# External_Camera_HAT_Peripherals.net
KiCad netlist of a schematic drawn in Altium Designer
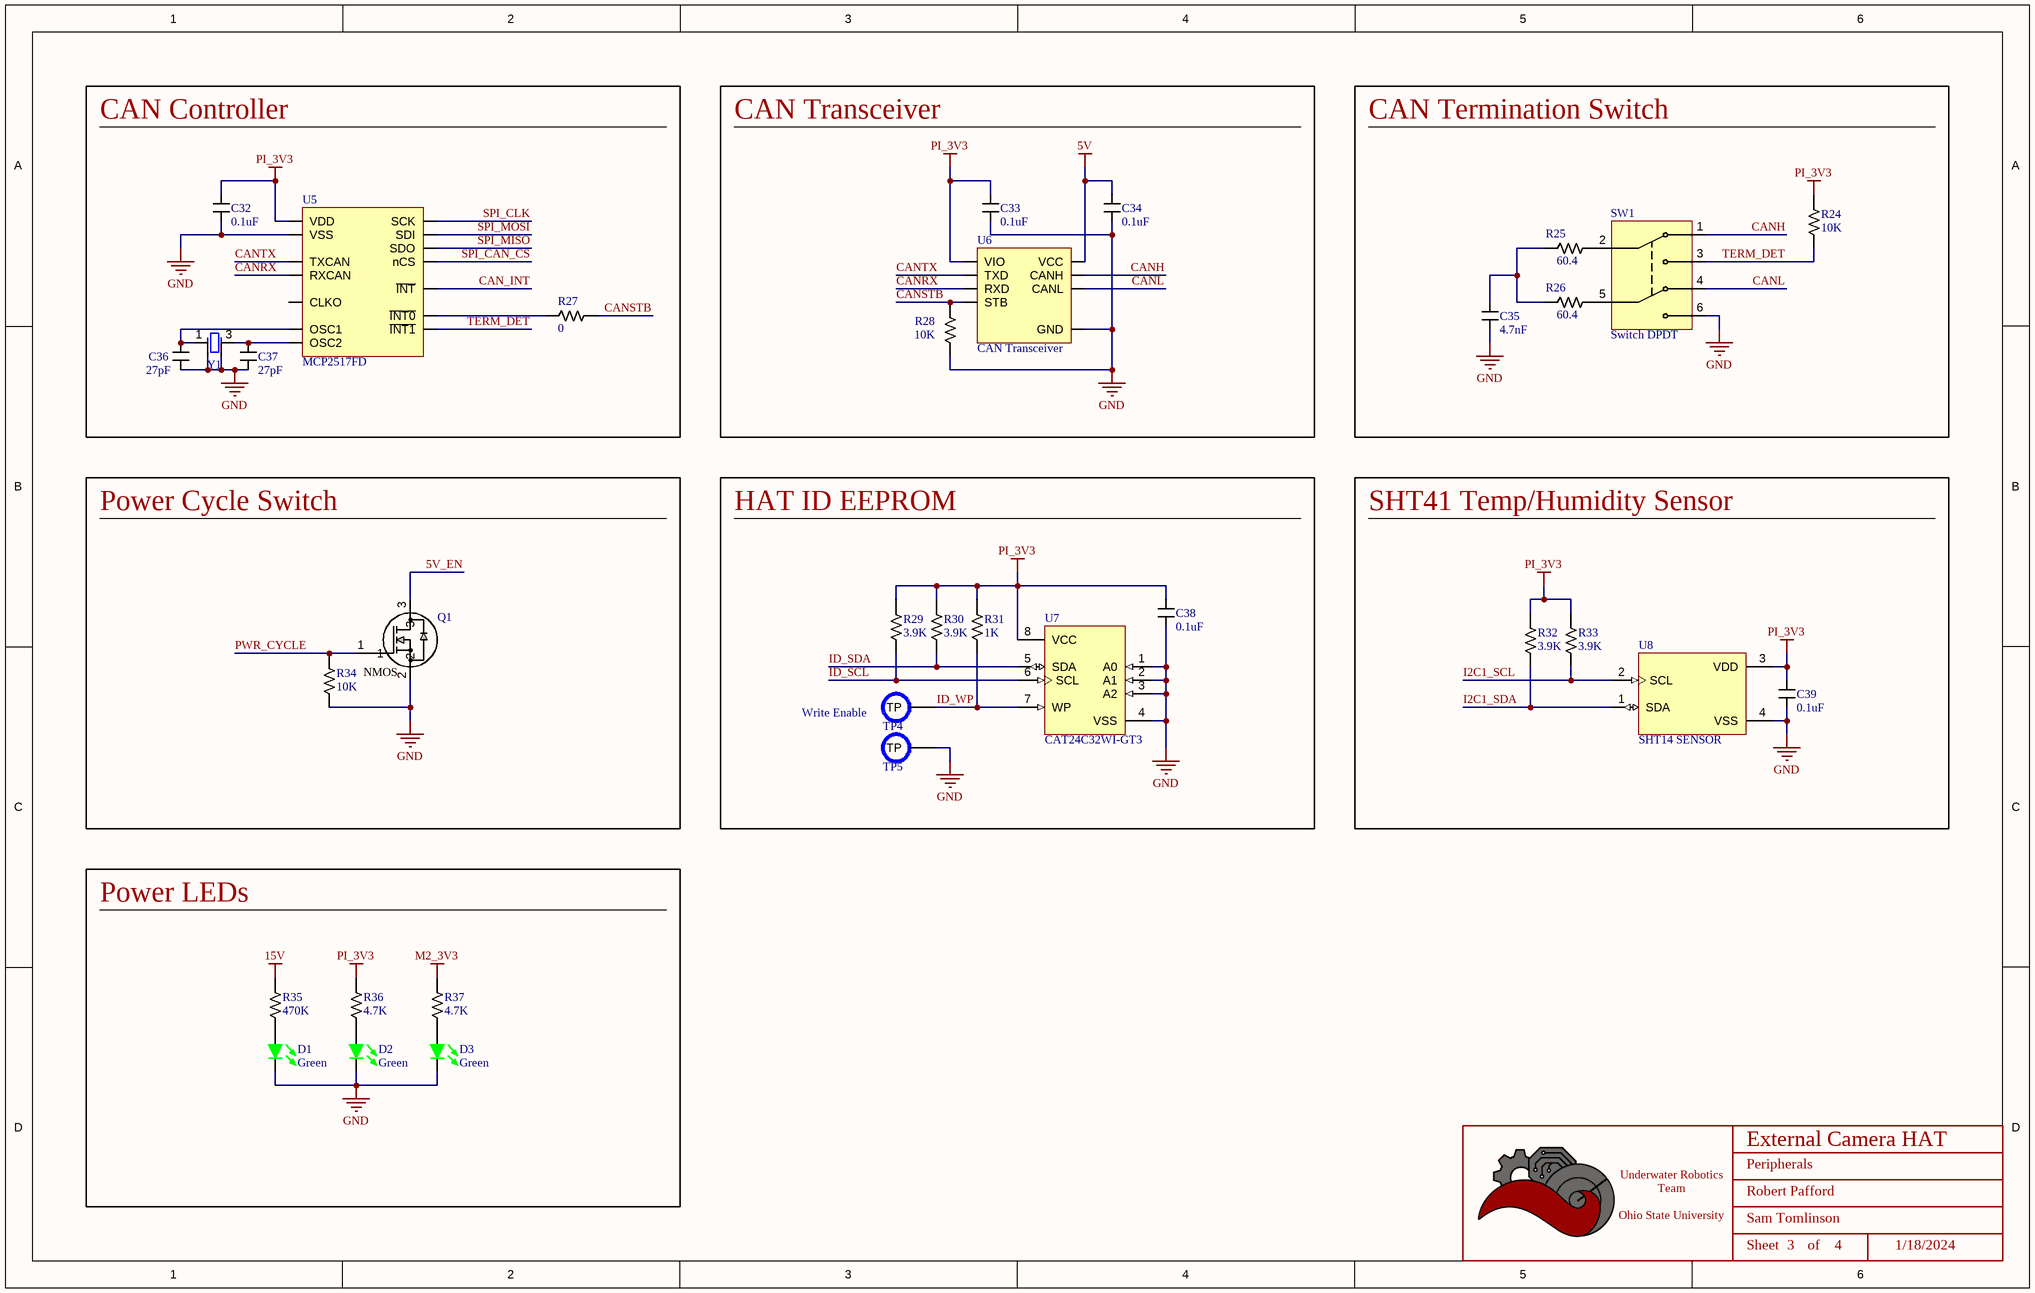
[diagram p0: External_Camera_HAT_Peripherals.SchDoc]

(export (version "E")
  (design (tool "Eeschema 10.0.6"))
  (components
    (comp (ref "C32")
      (value "0.1uF")
      (footprint "CAPACITOR_0402")
      (description "Cap 100nF 25V +/-10%\r\nCeramic 0402")
      (fields
        (field (name "TOLERANCE") "+/- 10%")
        (field (name "VOLTAGE") "25V")
        (field (name "MADE BY") "Robert Pafford")
      )
      (libsource (lib "Capacitors") (part "CAPACITOR_0.1uF_0402"))
    )
    (comp (ref "C33")
      (value "0.1uF")
      (footprint "CAPACITOR_0402")
      (description "Cap 100nF 25V +/-10%\r\nCeramic 0402")
      (fields
        (field (name "TOLERANCE") "+/- 10%")
        (field (name "VOLTAGE") "25V")
        (field (name "MADE BY") "Robert Pafford")
      )
      (libsource (lib "Capacitors") (part "CAPACITOR_0.1uF_0402"))
    )
    (comp (ref "C34")
      (value "0.1uF")
      (footprint "CAPACITOR_0402")
      (description "Cap 100nF 25V +/-10%\r\nCeramic 0402")
      (fields
        (field (name "TOLERANCE") "+/- 10%")
        (field (name "VOLTAGE") "25V")
        (field (name "MADE BY") "Robert Pafford")
      )
      (libsource (lib "Capacitors") (part "CAPACITOR_0.1uF_0402"))
    )
    (comp (ref "C35")
      (value "4.7nF")
      (footprint "CAPACITOR_0402")
      (description "4700 pF +/-10% 25V Ceramic Capacitor X7R 0402")
      (fields
        (field (name "TOLERANCE") "+/- 10%")
        (field (name "VOLTAGE") "25V")
        (field (name "MADE BY") "Robert Pafford")
      )
      (libsource (lib "Capacitors") (part "CAPACITOR_0.0047uF_0402"))
    )
    (comp (ref "C36")
      (value "27pF")
      (footprint "CAPACITOR_0402")
      (description "Cap 27pF 50V +/-5%\r\nCeramic 0402")
      (fields
        (field (name "TOLERANCE") "+/- 5%")
        (field (name "VOLTAGE") "50V")
        (field (name "MADE BY") "Robert Pafford")
      )
      (libsource (lib "Capacitors") (part "CAPACITOR_0.000027uF_0402"))
    )
    (comp (ref "C37")
      (value "27pF")
      (footprint "CAPACITOR_0402")
      (description "Cap 27pF 50V +/-5%\r\nCeramic 0402")
      (fields
        (field (name "TOLERANCE") "+/- 5%")
        (field (name "VOLTAGE") "50V")
        (field (name "MADE BY") "Robert Pafford")
      )
      (libsource (lib "Capacitors") (part "CAPACITOR_0.000027uF_0402"))
    )
    (comp (ref "C38")
      (value "0.1uF")
      (footprint "CAPACITOR_0402")
      (description "Cap 100nF 25V +/-10%\r\nCeramic 0402")
      (fields
        (field (name "TOLERANCE") "+/- 10%")
        (field (name "VOLTAGE") "25V")
        (field (name "MADE BY") "Robert Pafford")
      )
      (libsource (lib "Capacitors") (part "CAPACITOR_0.1uF_0402"))
    )
    (comp (ref "C39")
      (value "0.1uF")
      (footprint "CAPACITOR_0402")
      (description "Cap 100nF 25V +/-10%\r\nCeramic 0402")
      (fields
        (field (name "TOLERANCE") "+/- 10%")
        (field (name "VOLTAGE") "25V")
        (field (name "MADE BY") "Robert Pafford")
      )
      (libsource (lib "Capacitors") (part "CAPACITOR_0.1uF_0402"))
    )
    (comp (ref "D1")
      (value "150060GS75000")
      (footprint "LED_0603")
      (description "LED Green Vf= 3.2V If = 0.025A\r\n150060GS75000")
      (fields (field (name "COLOR") "Green") (field (name "MADE BY") "Flip B"))
      (libsource (lib "Diodes") (part "LED_Green_0603_3.2V"))
    )
    (comp (ref "D2")
      (value "150060GS75000")
      (footprint "LED_0603")
      (description "LED Green Vf= 3.2V If = 0.025A\r\n150060GS75000")
      (fields (field (name "COLOR") "Green") (field (name "MADE BY") "Flip B"))
      (libsource (lib "Diodes") (part "LED_Green_0603_3.2V"))
    )
    (comp (ref "D3")
      (value "150060GS75000")
      (footprint "LED_0603")
      (description "LED Green Vf= 3.2V If = 0.025A\r\n150060GS75000")
      (fields (field (name "COLOR") "Green") (field (name "MADE BY") "Flip B"))
      (libsource (lib "Diodes") (part "LED_Green_0603_3.2V"))
    )
    (comp (ref "Q1")
      (value "MOSFET N-CH 30V 5.8A SOT-23-3")
      (footprint "SOT-23-3")
      (description "N-Channel 30 V 5.8A (Ta) 1.4W (Ta) Surface Mount SOT-23-3")
      (fields (field (name "MANUFACTURER _PART_NUMBER") "AO3404A") (field (name "CREATED BY") "Dylan T"))
      (libsource (lib "Transistors") (part "AO3404A"))
    )
    (comp (ref "R24")
      (value "10k Ohm 1% 1/16W")
      (footprint "RESISTOR_0402")
      (description "RES 10k OHM 1% 1/16W 0402")
      (fields
        (field (name "TOLERANCE") "+/- 1%")
        (field (name "VALUE  (OHMS)") "10K")
        (field (name "MADE BY") "Robert Pafford")
      )
      (libsource (lib "Resistors") (part "RESISTOR_10K_0402"))
    )
    (comp (ref "R25")
      (value "60.4 Ohm 1% 1/16W")
      (footprint "RESISTOR_0402")
      (description "RES 60.4 OHM 1% 1/16W 0402")
      (fields
        (field (name "TOLERANCE") "+/- 1%")
        (field (name "VALUE  (OHMS)") "60.4")
        (field (name "MADE BY") "Robert Pafford")
      )
      (libsource (lib "Resistors") (part "RESISTOR_60.4_0402"))
    )
    (comp (ref "R26")
      (value "60.4 Ohm 1% 1/16W")
      (footprint "RESISTOR_0402")
      (description "RES 60.4 OHM 1% 1/16W 0402")
      (fields
        (field (name "TOLERANCE") "+/- 1%")
        (field (name "VALUE  (OHMS)") "60.4")
        (field (name "MADE BY") "Robert Pafford")
      )
      (libsource (lib "Resistors") (part "RESISTOR_60.4_0402"))
    )
    (comp (ref "R27")
      (value "0 Ohm 1% 1/16W")
      (footprint "RESISTOR_0402")
      (description "RES 0 OHM 1% 1/16W 0402")
      (fields
        (field (name "TOLERANCE") "+/- 1%")
        (field (name "VALUE  (OHMS)") "0")
        (field (name "MADE BY") "Robert Pafford")
      )
      (libsource (lib "Resistors") (part "RESISTOR_0_0402"))
    )
    (comp (ref "R28")
      (value "10k Ohm 1% 1/16W")
      (footprint "RESISTOR_0402")
      (description "RES 10k OHM 1% 1/16W 0402")
      (fields
        (field (name "TOLERANCE") "+/- 1%")
        (field (name "VALUE  (OHMS)") "10K")
        (field (name "MADE BY") "Robert Pafford")
      )
      (libsource (lib "Resistors") (part "RESISTOR_10K_0402"))
    )
    (comp (ref "R29")
      (value "3.9k Ohm 1% 1/16W")
      (footprint "RESISTOR_0402")
      (description "RES 3.9k OHM 1% 1/16W 0402")
      (fields
        (field (name "TOLERANCE") "+/- 1%")
        (field (name "VALUE  (OHMS)") "3.9K")
        (field (name "MADE BY") "Robert Pafford")
      )
      (libsource (lib "Resistors") (part "RESISTOR_3.9K_0402"))
    )
    (comp (ref "R30")
      (value "3.9k Ohm 1% 1/16W")
      (footprint "RESISTOR_0402")
      (description "RES 3.9k OHM 1% 1/16W 0402")
      (fields
        (field (name "TOLERANCE") "+/- 1%")
        (field (name "VALUE  (OHMS)") "3.9K")
        (field (name "MADE BY") "Robert Pafford")
      )
      (libsource (lib "Resistors") (part "RESISTOR_3.9K_0402"))
    )
    (comp (ref "R31")
      (value "1k Ohm 1% 1/16W")
      (footprint "RESISTOR_0402")
      (description "RES 1k OHM 1% 1/16W 0402")
      (fields
        (field (name "TOLERANCE") "+/- 1%")
        (field (name "VALUE  (OHMS)") "1K")
        (field (name "MADE BY") "Robert Pafford")
      )
      (libsource (lib "Resistors") (part "RESISTOR_1K_0402"))
    )
    (comp (ref "R32")
      (value "3.9k Ohm 1% 1/16W")
      (footprint "RESISTOR_0402")
      (description "RES 3.9k OHM 1% 1/16W 0402")
      (fields
        (field (name "TOLERANCE") "+/- 1%")
        (field (name "VALUE  (OHMS)") "3.9K")
        (field (name "MADE BY") "Robert Pafford")
      )
      (libsource (lib "Resistors") (part "RESISTOR_3.9K_0402"))
    )
    (comp (ref "R33")
      (value "3.9k Ohm 1% 1/16W")
      (footprint "RESISTOR_0402")
      (description "RES 3.9k OHM 1% 1/16W 0402")
      (fields
        (field (name "TOLERANCE") "+/- 1%")
        (field (name "VALUE  (OHMS)") "3.9K")
        (field (name "MADE BY") "Robert Pafford")
      )
      (libsource (lib "Resistors") (part "RESISTOR_3.9K_0402"))
    )
    (comp (ref "R34")
      (value "10k Ohm 1% 1/16W")
      (footprint "RESISTOR_0402")
      (description "RES 10k OHM 1% 1/16W 0402")
      (fields
        (field (name "TOLERANCE") "+/- 1%")
        (field (name "VALUE  (OHMS)") "10K")
        (field (name "MADE BY") "Robert Pafford")
      )
      (libsource (lib "Resistors") (part "RESISTOR_10K_0402"))
    )
    (comp (ref "R35")
      (value "470k Ohm 5% 1/10W")
      (footprint "RESISTOR_0603")
      (description "RES 470k OHM 5% 1/10W 0603")
      (fields
        (field (name "TOLERANCE") "+/- 5%")
        (field (name "VALUE  (OHMS)") "470K")
        (field (name "MADE BY") "Robert P")
      )
      (libsource (lib "Resistors") (part "RESISTOR_470K_0603"))
    )
    (comp (ref "R36")
      (value "4.7k Ohm 5% 1/10W")
      (footprint "RESISTOR_0603")
      (description "RES 4.7k OHM 5% 1/10W 0603")
      (fields
        (field (name "TOLERANCE") "+/- 5%")
        (field (name "VALUE  (OHMS)") "4.7K")
        (field (name "MADE BY") "Robert Pafford")
      )
      (libsource (lib "Resistors") (part "RESISTOR_4.7K_0603"))
    )
    (comp (ref "R37")
      (value "4.7k Ohm 5% 1/10W")
      (footprint "RESISTOR_0603")
      (description "RES 4.7k OHM 5% 1/10W 0603")
      (fields
        (field (name "TOLERANCE") "+/- 5%")
        (field (name "VALUE  (OHMS)") "4.7K")
        (field (name "MADE BY") "Robert Pafford")
      )
      (libsource (lib "Resistors") (part "RESISTOR_4.7K_0603"))
    )
    (comp (ref "SW1")
      (value "Switch DPDT")
      (footprint "CAS-220TA")
      (description "GOLD SWITCH FLUSH SLIDE DPDT 100MA 6V")
      (fields (field (name "MADE BY") "Robert Pafford"))
      (libsource (lib "Switches") (part "CAS-220TA_CAN_TERM"))
    )
    (comp (ref "TP4")
      (value "Write Enable")
      (footprint "TESTPOINT_1.2MM")
      (description "PCB Test Point")
      (fields (field (name "MADE BY") "Robert Pafford"))
      (libsource (lib "Connectors") (part "TESTPOINT"))
    )
    (comp (ref "TP5")
      (value "PCB Test Point")
      (footprint "TESTPOINT_1.2MM")
      (fields (field (name "MADE BY") "Robert Pafford"))
      (libsource (lib "Connectors") (part "TESTPOINT"))
    )
    (comp (ref "U5")
      (value "MCP2517FD")
      (footprint "SOIC-14")
      (description "CANbus Controller CAN 2.0 SPI Interface 14-SOIC")
      (fields (field (name "MADE BY") "Robert Pafford"))
      (libsource (lib "Integrated Circuits") (part "MCP2517FD"))
    )
    (comp (ref "U6")
      (value "CAN Transceiver")
      (footprint "SOIC-8")
      (description "CAN Interface IC High-Speed CAN Transceiver with Standby Mode")
      (fields (field (name "MADE BY") "Robert Pafford"))
      (libsource (lib "Integrated Circuits") (part "TJA1442AT"))
    )
    (comp (ref "U7")
      (value "CAT24C32WI-GT3")
      (footprint "ONSC-SOIC-8-751BD-01_M")
      (libsource (lib "Altium Content Vault") (part "ONSC-CAT24C32-SOIC-8"))
    )
    (comp (ref "U8")
      (value "SHT14 SENSOR")
      (footprint "XDCR_SHT41-AD1B-R2")
      (description "Digital Relative Humidity Temperature Sensor, Â±1.8 / max 2.5 %RH, Â±0.2 Â°C, Ultra-Low-Power")
      (fields (field (name "MP") "SHT41-AD1B-R2") (field (name "MF") "Sensirion"))
      (libsource (lib "Integrated Circuits") (part "SHT41-AD1B-R2"))
    )
    (comp (ref "Y1")
      (value "CRYSTAL 20.0000MHZ 18PF SMD")
      (footprint "4-SMD, NO LEAD CRYSTAL 3.2x2.5mm")
      (description "20 MHz ±20ppm Crystal 18pF 100 Ohms 4-SMD, No Lead (3.2x2.5mm)")
      (fields (field (name "MADE BY") "Robert Pafford"))
      (libsource (lib "Crystals") (part "CRYSTAL_20MHz_SMD"))
    )
  )
  (nets
    (net (code "1") (name "/5V_EN") (class "Default")
      (node (ref "Q1") (pin "3") (pinfunction "3_3") (pintype "passive"))
    )
    (net (code "2") (name "/CANH") (class "Default")
      (node (ref "SW1") (pin "1") (pintype "passive"))
      (node (ref "U6") (pin "7") (pinfunction "CANH_7") (pintype "passive"))
    )
    (net (code "3") (name "/CANL") (class "Default")
      (node (ref "SW1") (pin "4") (pintype "passive"))
      (node (ref "U6") (pin "6") (pinfunction "CANL_6") (pintype "passive"))
    )
    (net (code "4") (name "/CANRX") (class "Default")
      (node (ref "U5") (pin "2") (pinfunction "RXCAN_2") (pintype "passive"))
      (node (ref "U6") (pin "4") (pinfunction "RXD_4") (pintype "passive"))
    )
    (net (code "5") (name "/CANSTB") (class "Default")
      (node (ref "R27") (pin "1") (pinfunction "1_1") (pintype "passive"))
      (node (ref "R28") (pin "1") (pinfunction "1_1") (pintype "passive"))
      (node (ref "U6") (pin "8") (pinfunction "STB_8") (pintype "passive"))
    )
    (net (code "6") (name "/CANTX") (class "Default")
      (node (ref "U5") (pin "1") (pinfunction "TXCAN_1") (pintype "passive"))
      (node (ref "U6") (pin "1") (pinfunction "TXD_1") (pintype "passive"))
    )
    (net (code "7") (name "/CAN_INT") (class "Default")
      (node (ref "U5") (pin "4") (pinfunction "~{INT}_4") (pintype "passive"))
    )
    (net (code "8") (name "/I2C1_SCL") (class "Default")
      (node (ref "R33") (pin "2") (pinfunction "2_2") (pintype "passive"))
      (node (ref "U8") (pin "2") (pinfunction "SCL_2") (pintype "input"))
    )
    (net (code "9") (name "/I2C1_SDA") (class "Default")
      (node (ref "R32") (pin "2") (pinfunction "2_2") (pintype "passive"))
      (node (ref "U8") (pin "1") (pinfunction "SDA_1") (pintype "bidirectional"))
    )
    (net (code "10") (name "/ID_SCL") (class "Default")
      (node (ref "R29") (pin "2") (pinfunction "2_2") (pintype "passive"))
      (node (ref "U7") (pin "6") (pinfunction "SCL_6") (pintype "input"))
    )
    (net (code "11") (name "/ID_SDA") (class "Default")
      (node (ref "R30") (pin "2") (pinfunction "2_2") (pintype "passive"))
      (node (ref "U7") (pin "5") (pinfunction "SDA_5") (pintype "bidirectional"))
    )
    (net (code "12") (name "/ID_WP") (class "Default")
      (node (ref "R31") (pin "2") (pinfunction "2_2") (pintype "passive"))
      (node (ref "TP4") (pin "TP") (pinfunction "TP_TP") (pintype "passive"))
      (node (ref "U7") (pin "7") (pinfunction "WP_7") (pintype "input"))
    )
    (net (code "13") (name "/PWR_CYCLE") (class "Default")
      (node (ref "Q1") (pin "1") (pinfunction "1_1") (pintype "passive"))
      (node (ref "R34") (pin "1") (pinfunction "1_1") (pintype "passive"))
    )
    (net (code "14") (name "/SPI_CAN_CS") (class "Default")
      (node (ref "U5") (pin "13") (pinfunction "nCS_13") (pintype "passive"))
    )
    (net (code "15") (name "/SPI_CLK") (class "Default")
      (node (ref "U5") (pin "10") (pinfunction "SCK_10") (pintype "passive"))
    )
    (net (code "16") (name "/SPI_MISO") (class "Default")
      (node (ref "U5") (pin "12") (pinfunction "SDO_12") (pintype "passive"))
    )
    (net (code "17") (name "/SPI_MOSI") (class "Default")
      (node (ref "U5") (pin "11") (pinfunction "SDI_11") (pintype "passive"))
    )
    (net (code "18") (name "/TERM_DET") (class "Default")
      (node (ref "R24") (pin "2") (pinfunction "2_2") (pintype "passive"))
      (node (ref "SW1") (pin "3") (pintype "passive"))
      (node (ref "U5") (pin "8") (pinfunction "~{INT1}_8") (pintype "passive"))
    )
    (net (code "19") (name "5V") (class "Default")
      (node (ref "C34") (pin "1") (pinfunction "1_1") (pintype "passive"))
      (node (ref "U6") (pin "3") (pinfunction "VCC_3") (pintype "passive"))
    )
    (net (code "20") (name "15V") (class "Default")
      (node (ref "R35") (pin "1") (pinfunction "1_1") (pintype "passive"))
    )
    (net (code "21") (name "GND") (class "Default")
      (node (ref "C32") (pin "2") (pinfunction "2_2") (pintype "passive"))
      (node (ref "C33") (pin "2") (pinfunction "2_2") (pintype "passive"))
      (node (ref "C34") (pin "2") (pinfunction "2_2") (pintype "passive"))
      (node (ref "C35") (pin "1") (pinfunction "1_1") (pintype "passive"))
      (node (ref "C36") (pin "2") (pinfunction "2_2") (pintype "passive"))
      (node (ref "C37") (pin "2") (pinfunction "2_2") (pintype "passive"))
      (node (ref "C38") (pin "2") (pinfunction "2_2") (pintype "passive"))
      (node (ref "C39") (pin "2") (pinfunction "2_2") (pintype "passive"))
      (node (ref "D1") (pin "2") (pinfunction "2_2") (pintype "passive"))
      (node (ref "D2") (pin "2") (pinfunction "2_2") (pintype "passive"))
      (node (ref "D3") (pin "2") (pinfunction "2_2") (pintype "passive"))
      (node (ref "Q1") (pin "2") (pinfunction "2_2") (pintype "passive"))
      (node (ref "R28") (pin "2") (pinfunction "2_2") (pintype "passive"))
      (node (ref "R34") (pin "2") (pinfunction "2_2") (pintype "passive"))
      (node (ref "SW1") (pin "6") (pintype "passive"))
      (node (ref "TP5") (pin "TP") (pinfunction "TP_TP") (pintype "passive"))
      (node (ref "U5") (pin "7") (pinfunction "VSS_7") (pintype "passive"))
      (node (ref "U6") (pin "2") (pinfunction "GND_2") (pintype "passive"))
      (node (ref "U7") (pin "1") (pinfunction "A0_1") (pintype "input"))
      (node (ref "U7") (pin "2") (pinfunction "A1_2") (pintype "input"))
      (node (ref "U7") (pin "3") (pinfunction "A2_3") (pintype "input"))
      (node (ref "U7") (pin "4") (pinfunction "VSS_4") (pintype "power_in"))
      (node (ref "U8") (pin "4") (pinfunction "VSS_4") (pintype "power_in"))
      (node (ref "Y1") (pin "2") (pinfunction "GND1_2") (pintype "power_in"))
      (node (ref "Y1") (pin "4") (pinfunction "GND1_4") (pintype "power_in"))
    )
    (net (code "22") (name "M2_3V3") (class "Default")
      (node (ref "R37") (pin "1") (pinfunction "1_1") (pintype "passive"))
    )
    (net (code "23") (name "Net-(C35-Pad2)") (class "Default")
      (node (ref "C35") (pin "2") (pinfunction "2_2") (pintype "passive"))
      (node (ref "R25") (pin "2") (pinfunction "2_2") (pintype "passive"))
      (node (ref "R26") (pin "2") (pinfunction "2_2") (pintype "passive"))
    )
    (net (code "24") (name "Net-(D1-Pad1)") (class "Default")
      (node (ref "D1") (pin "1") (pinfunction "1_1") (pintype "passive"))
      (node (ref "R35") (pin "2") (pinfunction "2_2") (pintype "passive"))
    )
    (net (code "25") (name "Net-(D2-Pad1)") (class "Default")
      (node (ref "D2") (pin "1") (pinfunction "1_1") (pintype "passive"))
      (node (ref "R36") (pin "2") (pinfunction "2_2") (pintype "passive"))
    )
    (net (code "26") (name "Net-(D3-Pad1)") (class "Default")
      (node (ref "D3") (pin "1") (pinfunction "1_1") (pintype "passive"))
      (node (ref "R37") (pin "2") (pinfunction "2_2") (pintype "passive"))
    )
    (net (code "27") (name "Net-(R25-Pad1)") (class "Default")
      (node (ref "R25") (pin "1") (pinfunction "1_1") (pintype "passive"))
      (node (ref "SW1") (pin "2") (pintype "passive"))
    )
    (net (code "28") (name "Net-(R26-Pad1)") (class "Default")
      (node (ref "R26") (pin "1") (pinfunction "1_1") (pintype "passive"))
      (node (ref "SW1") (pin "5") (pintype "passive"))
    )
    (net (code "29") (name "Net-(U5-OSC1)") (class "Default")
      (node (ref "C36") (pin "1") (pinfunction "1_1") (pintype "passive"))
      (node (ref "U5") (pin "6") (pinfunction "OSC1_6") (pintype "passive"))
      (node (ref "Y1") (pin "1") (pinfunction "1_1") (pintype "passive"))
    )
    (net (code "30") (name "Net-(U5-OSC2)") (class "Default")
      (node (ref "C37") (pin "1") (pinfunction "1_1") (pintype "passive"))
      (node (ref "U5") (pin "5") (pinfunction "OSC2_5") (pintype "passive"))
      (node (ref "Y1") (pin "3") (pinfunction "3_3") (pintype "passive"))
    )
    (net (code "31") (name "Net-(U5-~{INT0})") (class "Default")
      (node (ref "R27") (pin "2") (pinfunction "2_2") (pintype "passive"))
      (node (ref "U5") (pin "9") (pinfunction "~{INT0}_9") (pintype "passive"))
    )
    (net (code "32") (name "PI_3V3") (class "Default")
      (node (ref "C32") (pin "1") (pinfunction "1_1") (pintype "passive"))
      (node (ref "C33") (pin "1") (pinfunction "1_1") (pintype "passive"))
      (node (ref "C38") (pin "1") (pinfunction "1_1") (pintype "passive"))
      (node (ref "C39") (pin "1") (pinfunction "1_1") (pintype "passive"))
      (node (ref "R24") (pin "1") (pinfunction "1_1") (pintype "passive"))
      (node (ref "R29") (pin "1") (pinfunction "1_1") (pintype "passive"))
      (node (ref "R30") (pin "1") (pinfunction "1_1") (pintype "passive"))
      (node (ref "R31") (pin "1") (pinfunction "1_1") (pintype "passive"))
      (node (ref "R32") (pin "1") (pinfunction "1_1") (pintype "passive"))
      (node (ref "R33") (pin "1") (pinfunction "1_1") (pintype "passive"))
      (node (ref "R36") (pin "1") (pinfunction "1_1") (pintype "passive"))
      (node (ref "U5") (pin "14") (pinfunction "VDD_14") (pintype "passive"))
      (node (ref "U6") (pin "5") (pinfunction "VIO_5") (pintype "passive"))
      (node (ref "U7") (pin "8") (pinfunction "VCC_8") (pintype "power_in"))
      (node (ref "U8") (pin "3") (pinfunction "VDD_3") (pintype "power_in"))
    )
    (net (code "33") (name "unconnected-(U5-CLKO-Pad3)") (class "Default")
      (node (ref "U5") (pin "3") (pinfunction "CLKO_3") (pintype "passive"))
    )
  )
)
